# ESP32-3DE.net
KiCad netlist of a schematic drawn in Altium Designer
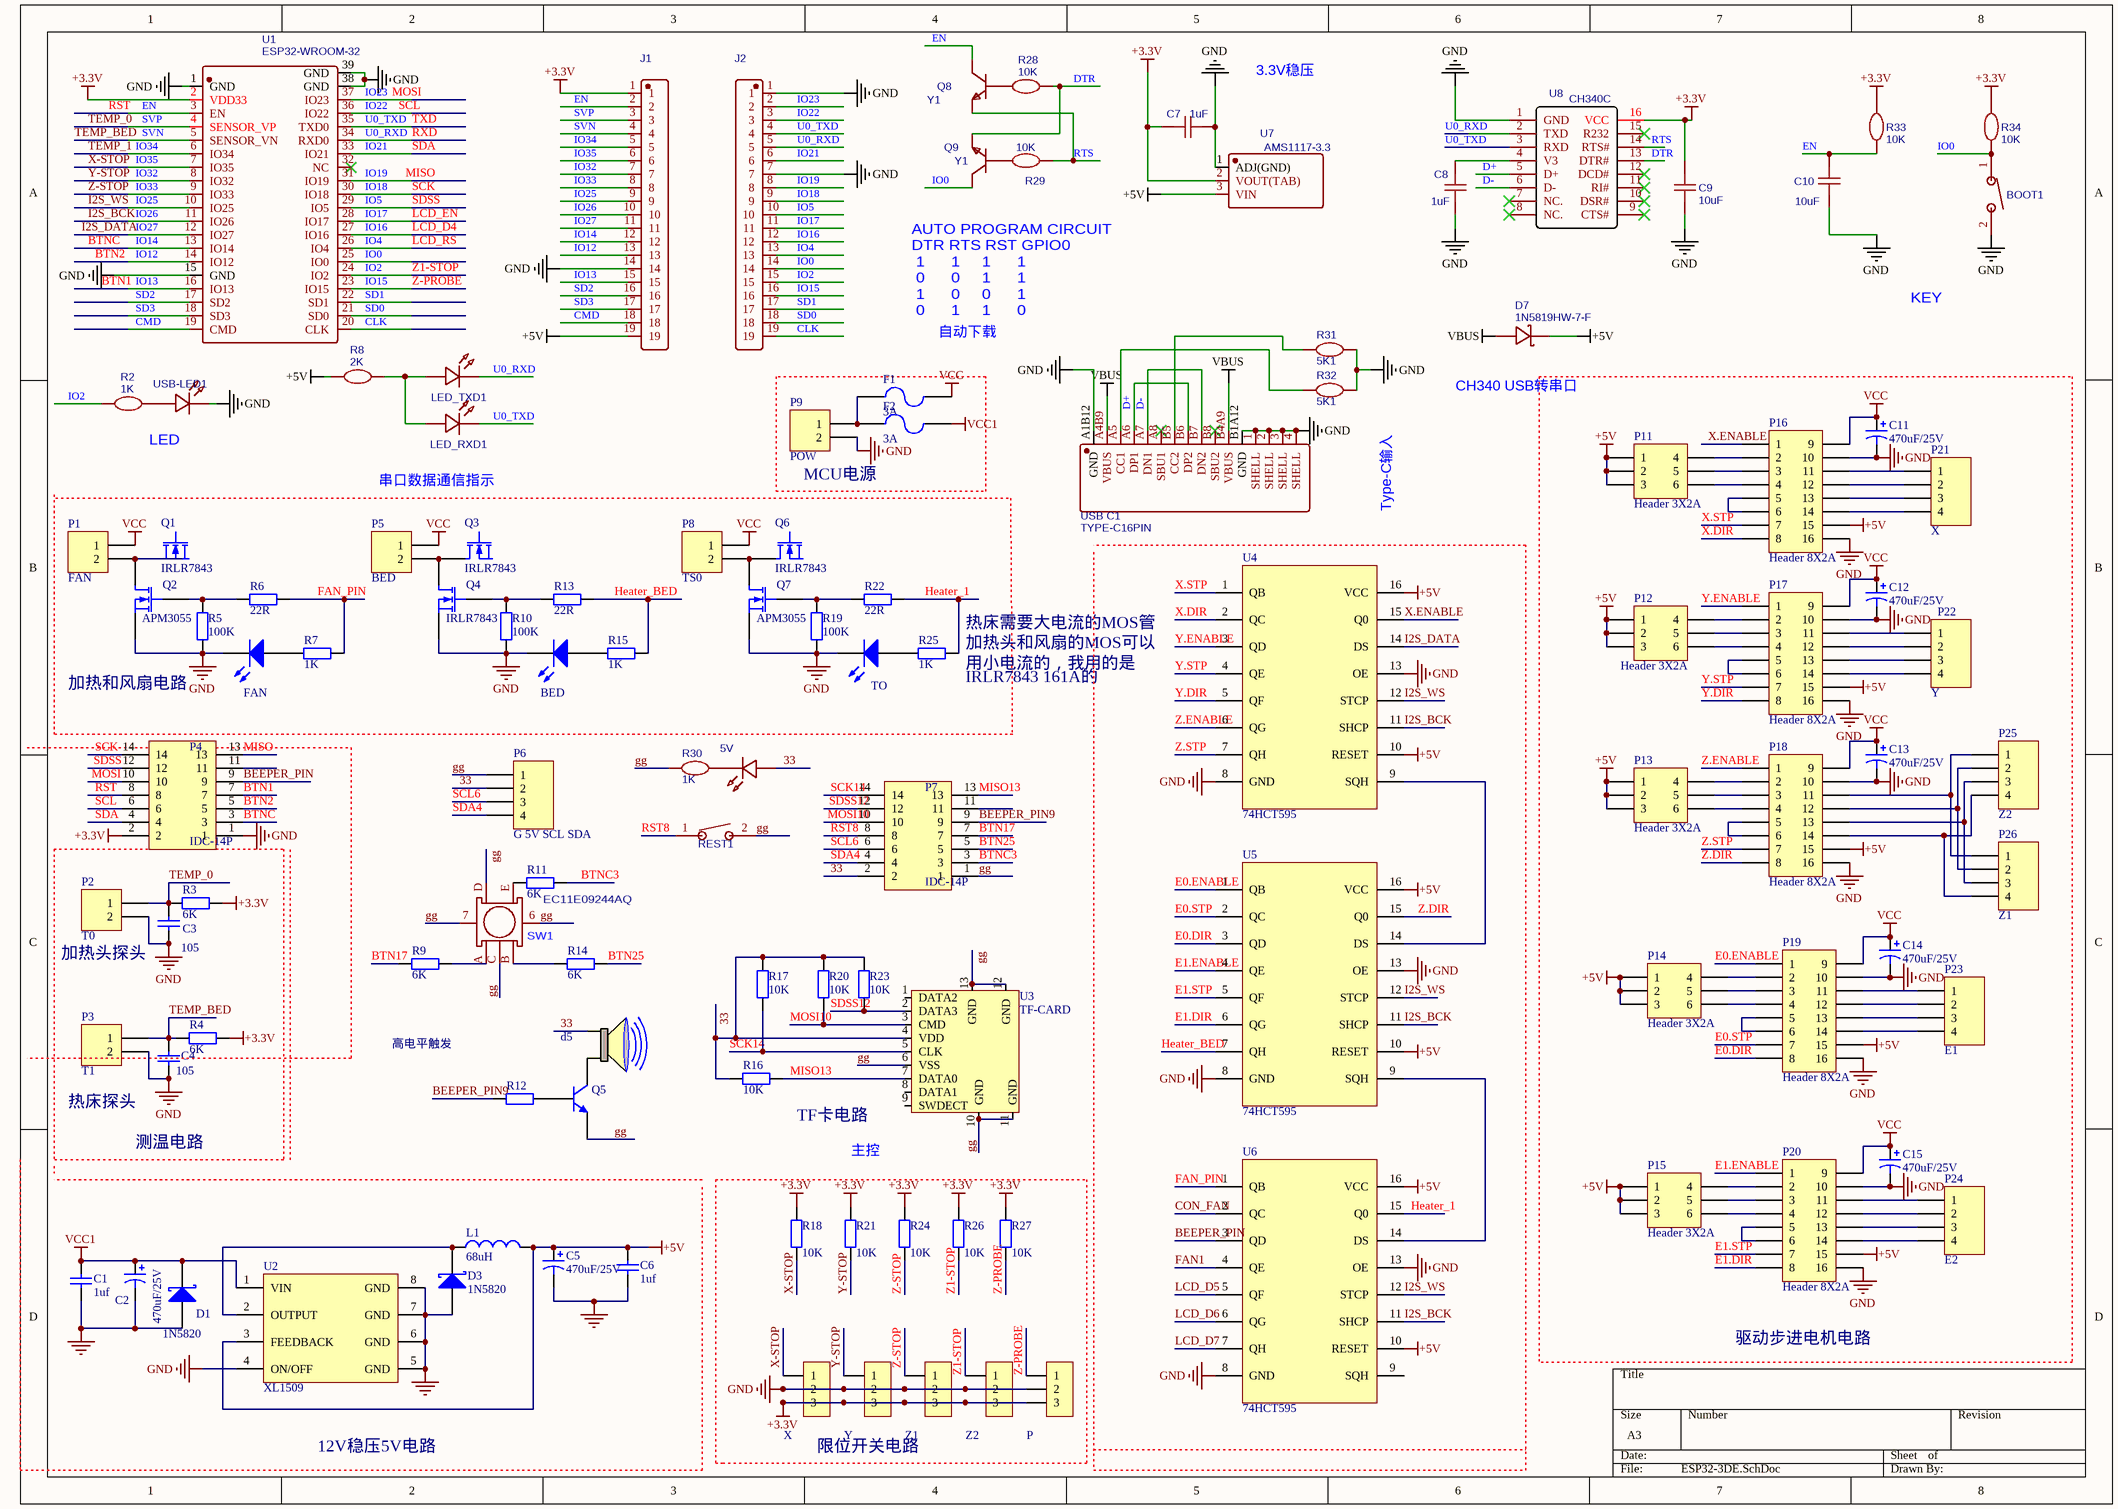
[diagram p0: ESP32-3DE.SchDoc]

(export (version "E")
  (design (tool "Eeschema 10.0.6"))
  (components
    (comp (ref "BOOT1")
      (value "BOOT")
      (footprint "SW-SMD_L4.0-W2.9-P4.15-EH")
      (fields
        (field (name "BOM_SUPPLIER PART") "C354947")
        (field (name "BOM_MANUFACTURER PART") "TSA343G00D-250J2")
        (field (name "CONTRIBUTOR") "LCSC")
      )
      (libsource (lib "altium-import") (part "root_3_TSA343G00D-250J2_"))
    )
    (comp (ref "C1")
      (value "1uf")
      (footprint "C0603")
      (description "Capacitor")
      (fields (field (name "PUBLISHER") "Altium Limited"))
      (libsource (lib "*") (part "Cap"))
    )
    (comp (ref "C2")
      (value "470uF/25V")
      (footprint "SMD-EC10X10X10")
      (description "Polarized Capacitor (Surface Mount)")
      (fields (field (name "PUBLISHER") "Altium Limited"))
      (libsource (lib "*") (part "Cap Pol3"))
    )
    (comp (ref "C3")
      (value "105")
      (footprint "C0603")
      (description "Capacitor")
      (fields (field (name "Comment") "1uf") (field (name "PUBLISHER") "Altium Limited"))
      (libsource (lib "Miscellaneous Devices") (part "Cap"))
    )
    (comp (ref "C4")
      (value "105")
      (footprint "C0603")
      (description "Capacitor")
      (fields (field (name "Comment") "1uf") (field (name "PUBLISHER") "Altium Limited"))
      (libsource (lib "Miscellaneous Devices") (part "Cap"))
    )
    (comp (ref "C5")
      (value "470uF/25V")
      (footprint "SMD-EC6.3X6.3X10")
      (description "Polarized Capacitor (Surface Mount)")
      (fields (field (name "PUBLISHER") "Altium Limited"))
      (libsource (lib "*") (part "Cap Pol3"))
    )
    (comp (ref "C6")
      (value "1uf")
      (footprint "C0603")
      (description "Capacitor")
      (fields (field (name "PUBLISHER") "Altium Limited"))
      (libsource (lib "*") (part "Cap"))
    )
    (comp (ref "C7")
      (value "1uF")
      (footprint "C0603")
      (fields (field (name "CONTRIBUTOR") "LCEDA_Lib"))
      (libsource (lib "altium-import") (part "root_0_10uF_"))
    )
    (comp (ref "C8")
      (value "1uF")
      (footprint "C0603")
      (fields
        (field (name "BOM_SUPPLIER PART") "C36577")
        (field (name "BOM_MANUFACTURER PART") "0603F105M250NT")
        (field (name "CONTRIBUTOR") "LCEDA_Lib")
      )
      (libsource (lib "altium-import") (part "root_1_1uF_"))
    )
    (comp (ref "C9")
      (value "10uF")
      (footprint "C0603")
      (fields (field (name "CONTRIBUTOR") "LCEDA_Lib"))
      (libsource (lib "altium-import") (part "root_1_10uF_"))
    )
    (comp (ref "C10")
      (value "10uF")
      (footprint "C0603")
      (fields (field (name "CONTRIBUTOR") "LCEDA_Lib"))
      (libsource (lib "altium-import") (part "root_1_10uF_"))
    )
    (comp (ref "C11")
      (value "470uF/25V")
      (footprint "SMD-EC6.3X6.3X10")
      (description "Polarized Capacitor (Radial)")
      (fields (field (name "Comment") "470UF") (field (name "PUBLISHER") "Altium Limited"))
      (libsource (lib "Miscellaneous Devices") (part "Cap Pol1"))
    )
    (comp (ref "C12")
      (value "470uF/25V")
      (footprint "SMD-EC6.3X6.3X10")
      (description "Polarized Capacitor (Radial)")
      (fields (field (name "Comment") "470UF") (field (name "PUBLISHER") "Altium Limited"))
      (libsource (lib "Miscellaneous Devices") (part "Cap Pol1"))
    )
    (comp (ref "C13")
      (value "470uF/25V")
      (footprint "SMD-EC6.3X6.3X10")
      (description "Polarized Capacitor (Radial)")
      (fields (field (name "Comment") "470UF") (field (name "PUBLISHER") "Altium Limited"))
      (libsource (lib "Miscellaneous Devices") (part "Cap Pol1"))
    )
    (comp (ref "C14")
      (value "470uF/25V")
      (footprint "SMD-EC6.3X6.3X10")
      (description "Polarized Capacitor (Radial)")
      (fields (field (name "Comment") "470UF") (field (name "PUBLISHER") "Altium Limited"))
      (libsource (lib "Miscellaneous Devices") (part "Cap Pol1"))
    )
    (comp (ref "C15")
      (value "470uF/25V")
      (footprint "SMD-EC6.3X6.3X10")
      (description "Polarized Capacitor (Radial)")
      (fields (field (name "Comment") "470UF") (field (name "PUBLISHER") "Altium Limited"))
      (libsource (lib "Miscellaneous Devices") (part "Cap Pol1"))
    )
    (comp (ref "D1")
      (value "1N5820")
      (footprint "SMA")
      (description "Schottky Diode")
      (fields (field (name "PUBLISHER") "Altium Limited"))
      (libsource (lib "Miscellaneous Devices") (part "D Schottky"))
    )
    (comp (ref "D2")
      (value "FAN")
      (footprint "LED 0603B")
      (description "Typical RED, GREEN, YELLOW, AMBER GaAs LED")
      (fields (field (name "PUBLISHER") "Altium Limited"))
      (libsource (lib "Miscellaneous Devices") (part "LED2"))
    )
    (comp (ref "D3")
      (value "1N5820")
      (footprint "SMA")
      (description "Schottky Diode")
      (fields (field (name "PUBLISHER") "Altium Limited"))
      (libsource (lib "Miscellaneous Devices") (part "D Schottky"))
    )
    (comp (ref "D4")
      (value "BED")
      (footprint "LED 0603B")
      (description "Typical RED, GREEN, YELLOW, AMBER GaAs LED")
      (fields (field (name "PUBLISHER") "Altium Limited"))
      (libsource (lib "Miscellaneous Devices") (part "LED2"))
    )
    (comp (ref "d5")
      (value "buzzer")
      (footprint "BEEP 5x9x5.5")
      (description "bu")
      (libsource (lib "YKY-arduinoRFID") (part "buzzer"))
    )
    (comp (ref "D6")
      (value "TO")
      (footprint "LED 0603B")
      (description "Typical RED, GREEN, YELLOW, AMBER GaAs LED")
      (fields (field (name "PUBLISHER") "Altium Limited"))
      (libsource (lib "Miscellaneous Devices") (part "LED2"))
    )
    (comp (ref "D7")
      (value "1N5819HW-7-F")
      (footprint "SOD-123_L2.8-W1.8-LS3.7-FD")
      (fields (field (name "BOM_SUPPLIER PART") "C82544"))
      (libsource (lib "altium-import") (part "root_0_1N5819HW-7-F_"))
    )
    (comp (ref "F1")
      (value "3A")
      (footprint "MCCQ-122")
      (description "Fuse")
      (fields (field (name "PUBLISHER") "Altium Limited"))
      (libsource (lib "Schlib1") (part "Fuse 2"))
    )
    (comp (ref "F2")
      (value "3A")
      (footprint "MCCQ-122")
      (description "Fuse")
      (fields (field (name "PUBLISHER") "Altium Limited"))
      (libsource (lib "Schlib1") (part "Fuse 2"))
    )
    (comp (ref "J1")
      (value "Header-Male-2.54_1x19")
      (footprint "HDR-TH_19P-P2.54-V-M-NOP")
      (fields
        (field (name "BOM_MANUFACTURER PART") "2.54mm 1*20PHeader")
        (field (name "BOM_SUPPLIER PART") "C50981")
        (field (name "CONTRIBUTOR") "shiyindebcd")
      )
      (libsource (lib "") (part "root_0_Header-Male-2.54_1x19__1"))
    )
    (comp (ref "J2")
      (value "Header-Male-2.54_1x19")
      (footprint "HDR-TH_19P-P2.54-V-M-NOP")
      (fields
        (field (name "BOM_MANUFACTURER PART") "2.54mm 1*20PHeader")
        (field (name "BOM_SUPPLIER PART") "C50981")
        (field (name "CONTRIBUTOR") "shiyindebcd")
      )
      (libsource (lib "altium-import") (part "root_0_Header-Male-2.54_1x19_"))
    )
    (comp (ref "JP1")
      (value "X")
      (footprint "XH2.54-LI-3P")
      (description "3P接插件")
      (fields (field (name "版权归属") "源创客"))
      (libsource (lib "Schlib1") (part "Header 3"))
    )
    (comp (ref "JP2")
      (value "Y")
      (footprint "XH2.54-LI-3P")
      (description "3P接插件")
      (fields (field (name "版权归属") "源创客"))
      (libsource (lib "Schlib1") (part "Header 3"))
    )
    (comp (ref "JP4")
      (value "Z1")
      (footprint "XH2.54-LI-3P")
      (description "3P接插件")
      (fields (field (name "版权归属") "源创客"))
      (libsource (lib "Schlib1") (part "Header 3"))
    )
    (comp (ref "JP5")
      (value "Z2")
      (footprint "XH2.54-LI-3P")
      (description "3P接插件")
      (fields (field (name "版权归属") "源创客"))
      (libsource (lib "Schlib1") (part "Header 3"))
    )
    (comp (ref "JP6")
      (value "P")
      (footprint "XH2.54-LI-3P")
      (description "3P接插件")
      (fields (field (name "版权归属") "源创客"))
      (libsource (lib "Schlib1") (part "Header 3"))
    )
    (comp (ref "L1")
      (value "68uH")
      (footprint "CDRH74")
      (description "Inductor")
      (fields (field (name "PUBLISHER") "Altium Limited"))
      (libsource (lib "*") (part "Inductor"))
    )
    (comp (ref "LED1")
      (value "5V")
      (footprint "LED 0603R")
      (fields
        (field (name "BOM_MANUFACTURER PART") "19-217/R6C-AL1M2VY/3T")
        (field (name "BOM_SUPPLIER PART") "C72044")
        (field (name "CONTRIBUTOR") "LCEDA_01")
      )
      (libsource (lib "altium-import") (part "root_2_IO2_"))
    )
    (comp (ref "LED_RXD1")
      (value "RXD")
      (footprint "LED 0603G")
      (fields
        (field (name "BOM_MANUFACTURER PART") "19-217/R6C-AL1M2VY/3T")
        (field (name "BOM_SUPPLIER PART") "C72044")
        (field (name "CONTRIBUTOR") "LCEDA_01")
      )
      (libsource (lib "altium-import") (part "root_0_RXD_"))
    )
    (comp (ref "LED_TXD1")
      (value "TXD")
      (footprint "LED 0603B")
      (fields
        (field (name "BOM_MANUFACTURER PART") "19-217/R6C-AL1M2VY/3T")
        (field (name "BOM_SUPPLIER PART") "C72044")
        (field (name "CONTRIBUTOR") "LCEDA_01")
      )
      (libsource (lib "altium-import") (part "root_0_TXD_"))
    )
    (comp (ref "P1")
      (value "FAN")
      (footprint "KF128-5.08-2P")
      (description "Header, 2-Pin")
      (fields (field (name "PUBLISHER") "Altium Limited"))
      (libsource (lib "Miscellaneous Connectors") (part "Header 2"))
    )
    (comp (ref "P2")
      (value "T0")
      (footprint "XH2.54-LI-2P")
      (description "Header, 2-Pin")
      (fields (field (name "PUBLISHER") "Altium Limited"))
      (libsource (lib "Miscellaneous Connectors") (part "Header 2"))
    )
    (comp (ref "P3")
      (value "T1")
      (footprint "XH2.54-LI-2P")
      (description "Header, 2-Pin")
      (fields (field (name "PUBLISHER") "Altium Limited"))
      (libsource (lib "Miscellaneous Connectors") (part "Header 2"))
    )
    (comp (ref "P4") (value "IDC-14P") (footprint "IDC2.54-14P") (libsource (lib "Schlib1") (part "IDC-14P")))
    (comp (ref "P5")
      (value "BED")
      (footprint "KF128-5.08-2P")
      (description "Header, 2-Pin")
      (fields (field (name "PUBLISHER") "Altium Limited"))
      (libsource (lib "Miscellaneous Connectors") (part "Header 2"))
    )
    (comp (ref "P6")
      (value "G 5V SCL SDA")
      (footprint "OLED-0.96-PIN4")
      (description "Header, 4-Pin")
      (fields (field (name "PUBLISHER") "Altium Limited"))
      (libsource (lib "Miscellaneous Connectors") (part "Header 4"))
    )
    (comp (ref "P7") (value "IDC-14P") (footprint "IDC2.54-14P") (libsource (lib "Schlib1") (part "IDC-14P")))
    (comp (ref "P8")
      (value "TS0")
      (footprint "KF128-5.08-2P")
      (description "Header, 2-Pin")
      (fields (field (name "PUBLISHER") "Altium Limited"))
      (libsource (lib "Miscellaneous Connectors") (part "Header 2"))
    )
    (comp (ref "P9")
      (value "POW")
      (footprint "KF128-5.08-2P")
      (description "Header, 2-Pin")
      (fields (field (name "PUBLISHER") "Altium Limited"))
      (libsource (lib "Miscellaneous Connectors") (part "Header 2"))
    )
    (comp (ref "P11")
      (value "Header 3X2A")
      (footprint "HDR2X3_CEN")
      (description "Header, 3-Pin, Dual row")
      (fields (field (name "PUBLISHER") "Altium Limited"))
      (libsource (lib "Miscellaneous Connectors") (part "Header 3X2A"))
    )
    (comp (ref "P12")
      (value "Header 3X2A")
      (footprint "HDR2X3_CEN")
      (description "Header, 3-Pin, Dual row")
      (fields (field (name "PUBLISHER") "Altium Limited"))
      (libsource (lib "Miscellaneous Connectors") (part "Header 3X2A"))
    )
    (comp (ref "P13")
      (value "Header 3X2A")
      (footprint "HDR2X3_CEN")
      (description "Header, 3-Pin, Dual row")
      (fields (field (name "PUBLISHER") "Altium Limited"))
      (libsource (lib "Miscellaneous Connectors") (part "Header 3X2A"))
    )
    (comp (ref "P14")
      (value "Header 3X2A")
      (footprint "HDR2X3_CEN")
      (description "Header, 3-Pin, Dual row")
      (fields (field (name "PUBLISHER") "Altium Limited"))
      (libsource (lib "Miscellaneous Connectors") (part "Header 3X2A"))
    )
    (comp (ref "P15")
      (value "Header 3X2A")
      (footprint "HDR2X3_CEN")
      (description "Header, 3-Pin, Dual row")
      (fields (field (name "PUBLISHER") "Altium Limited"))
      (libsource (lib "Miscellaneous Connectors") (part "Header 3X2A"))
    )
    (comp (ref "P16")
      (value "Header 8X2A")
      (footprint "A4988")
      (description "Header, 8-Pin, Dual row")
      (fields (field (name "PUBLISHER") "Altium Limited"))
      (libsource (lib "Miscellaneous Connectors") (part "Header 8X2A"))
    )
    (comp (ref "P17")
      (value "Header 8X2A")
      (footprint "A4988")
      (description "Header, 8-Pin, Dual row")
      (fields (field (name "PUBLISHER") "Altium Limited"))
      (libsource (lib "Miscellaneous Connectors") (part "Header 8X2A"))
    )
    (comp (ref "P18")
      (value "Header 8X2A")
      (footprint "A4988")
      (description "Header, 8-Pin, Dual row")
      (fields (field (name "PUBLISHER") "Altium Limited"))
      (libsource (lib "Miscellaneous Connectors") (part "Header 8X2A"))
    )
    (comp (ref "P19")
      (value "Header 8X2A")
      (footprint "A4988")
      (description "Header, 8-Pin, Dual row")
      (fields (field (name "PUBLISHER") "Altium Limited"))
      (libsource (lib "Miscellaneous Connectors") (part "Header 8X2A"))
    )
    (comp (ref "P20")
      (value "Header 8X2A")
      (footprint "A4988")
      (description "Header, 8-Pin, Dual row")
      (fields (field (name "PUBLISHER") "Altium Limited"))
      (libsource (lib "Miscellaneous Connectors") (part "Header 8X2A"))
    )
    (comp (ref "P21")
      (value "X")
      (footprint "XH2.54-LI-4P")
      (description "Header, 4-Pin")
      (fields (field (name "PUBLISHER") "Altium Limited"))
      (libsource (lib "Miscellaneous Connectors") (part "Header 4"))
    )
    (comp (ref "P22")
      (value "Y")
      (footprint "XH2.54-LI-4P")
      (description "Header, 4-Pin")
      (fields (field (name "PUBLISHER") "Altium Limited"))
      (libsource (lib "Miscellaneous Connectors") (part "Header 4"))
    )
    (comp (ref "P23")
      (value "E1")
      (footprint "XH2.54-LI-4P")
      (description "Header, 4-Pin")
      (fields (field (name "PUBLISHER") "Altium Limited"))
      (libsource (lib "Miscellaneous Connectors") (part "Header 4"))
    )
    (comp (ref "P24")
      (value "E2")
      (footprint "XH2.54-LI-4P")
      (description "Header, 4-Pin")
      (fields (field (name "PUBLISHER") "Altium Limited"))
      (libsource (lib "Miscellaneous Connectors") (part "Header 4"))
    )
    (comp (ref "P25")
      (value "Z2")
      (footprint "XH2.54-LI-4P")
      (description "Header, 4-Pin")
      (fields (field (name "PUBLISHER") "Altium Limited"))
      (libsource (lib "Miscellaneous Connectors") (part "Header 4"))
    )
    (comp (ref "P26")
      (value "Z1")
      (footprint "XH2.54-LI-4P")
      (description "Header, 4-Pin")
      (fields (field (name "PUBLISHER") "Altium Limited"))
      (libsource (lib "Miscellaneous Connectors") (part "Header 4"))
    )
    (comp (ref "Q1")
      (value "IRLR7843")
      (footprint "TO-252gk")
      (description "N-Channel MOSFET")
      (fields (field (name "PUBLISHER") "Altium Limited"))
      (libsource (lib "Schlib1") (part "MOSFET-Ngk"))
    )
    (comp (ref "Q2")
      (value "APM3055")
      (footprint "TO-252")
      (description "N-Channel MOSFET")
      (fields (field (name "PUBLISHER") "Altium Limited"))
      (libsource (lib "Miscellaneous Devices") (part "MOSFET-N"))
    )
    (comp (ref "Q3")
      (value "IRLR7843")
      (footprint "TO-252gk")
      (description "N-Channel MOSFET")
      (fields (field (name "PUBLISHER") "Altium Limited"))
      (libsource (lib "Schlib1") (part "MOSFET-Ngk"))
    )
    (comp (ref "Q4")
      (value "IRLR7843")
      (footprint "TO-252")
      (description "N-Channel MOSFET")
      (fields (field (name "PUBLISHER") "Altium Limited"))
      (libsource (lib "Miscellaneous Devices") (part "MOSFET-N"))
    )
    (comp (ref "Q5")
      (value "Y1")
      (footprint "SOT-23-3")
      (description "SS8050 Y1三极管")
      (libsource (lib "YKY-arduinoRFID") (part "SOT-23 SS8050 Y1"))
    )
    (comp (ref "Q6")
      (value "IRLR7843")
      (footprint "TO-252gk")
      (description "N-Channel MOSFET")
      (fields (field (name "PUBLISHER") "Altium Limited"))
      (libsource (lib "Schlib1") (part "MOSFET-Ngk"))
    )
    (comp (ref "Q7")
      (value "APM3055")
      (footprint "TO-252")
      (description "N-Channel MOSFET")
      (fields (field (name "PUBLISHER") "Altium Limited"))
      (libsource (lib "Miscellaneous Devices") (part "MOSFET-N"))
    )
    (comp (ref "Q8")
      (value "Y1")
      (footprint "SOT-23-3")
      (fields
        (field (name "BOM_SUPPLIER PART") "C2688231")
        (field (name "BOM_MANUFACTURER PART") "S8050")
        (field (name "CONTRIBUTOR") "LCSC")
      )
      (libsource (lib "altium-import") (part "root_0_S8050_"))
    )
    (comp (ref "Q9")
      (value "Y1")
      (footprint "SOT-23-3")
      (fields
        (field (name "BOM_SUPPLIER PART") "C2688231")
        (field (name "BOM_MANUFACTURER PART") "S8050")
        (field (name "CONTRIBUTOR") "LCSC")
      )
      (libsource (lib "altium-import") (part "root_2_S8050_"))
    )
    (comp (ref "R2")
      (value "1K")
      (footprint "R0603")
      (fields (field (name "CONTRIBUTOR") "LCEDA_Lib"))
      (libsource (lib "altium-import") (part "root_0_1K_"))
    )
    (comp (ref "R3")
      (value "6K")
      (footprint "R0603")
      (description "Resistor")
      (fields (field (name "PUBLISHER") "Altium Limited"))
      (libsource (lib "") (part "Res2_1"))
    )
    (comp (ref "R4")
      (value "6K")
      (footprint "R0603")
      (description "Resistor")
      (fields (field (name "PUBLISHER") "Altium Limited"))
      (libsource (lib "") (part "Res2_3"))
    )
    (comp (ref "R5")
      (value "100K")
      (footprint "R0603")
      (description "Resistor")
      (fields (field (name "PUBLISHER") "Altium Limited"))
      (libsource (lib "") (part "Res2_2"))
    )
    (comp (ref "R6")
      (value "22R")
      (footprint "R0603")
      (description "Resistor")
      (fields (field (name "PUBLISHER") "Altium Limited"))
      (libsource (lib "") (part "Res2_1"))
    )
    (comp (ref "R7")
      (value "1K")
      (footprint "R0603")
      (description "Resistor")
      (fields (field (name "PUBLISHER") "Altium Limited"))
      (libsource (lib "") (part "Res2_1"))
    )
    (comp (ref "R8")
      (value "2K")
      (footprint "R0603")
      (fields (field (name "CONTRIBUTOR") "LCEDA_Lib"))
      (libsource (lib "altium-import") (part "root_0_2K_"))
    )
    (comp (ref "R9")
      (value "6K")
      (footprint "R0603")
      (description "Resistor")
      (fields (field (name "PUBLISHER") "Altium Limited"))
      (libsource (lib "") (part "Res2_3"))
    )
    (comp (ref "R10")
      (value "100K")
      (footprint "R0603")
      (description "Resistor")
      (fields (field (name "PUBLISHER") "Altium Limited"))
      (libsource (lib "") (part "Res2_2"))
    )
    (comp (ref "R11")
      (value "6K")
      (footprint "R0603")
      (description "Resistor")
      (fields (field (name "PUBLISHER") "Altium Limited"))
      (libsource (lib "") (part "Res2_1"))
    )
    (comp (ref "R12")
      (value "4.7K")
      (footprint "R0603")
      (description "4.7KΩ (4701) ±1%贴片电阻")
      (libsource (lib "YKY-arduinoRFID") (part "0805 4.7KΩ (4701) 1%"))
    )
    (comp (ref "R13")
      (value "22R")
      (footprint "R0603")
      (description "Resistor")
      (fields (field (name "PUBLISHER") "Altium Limited"))
      (libsource (lib "") (part "Res2_1"))
    )
    (comp (ref "R14")
      (value "6K")
      (footprint "R0603")
      (description "Resistor")
      (fields (field (name "PUBLISHER") "Altium Limited"))
      (libsource (lib "") (part "Res2_3"))
    )
    (comp (ref "R15")
      (value "1K")
      (footprint "R0603")
      (description "Resistor")
      (fields (field (name "PUBLISHER") "Altium Limited"))
      (libsource (lib "") (part "Res2_1"))
    )
    (comp (ref "R16")
      (value "10K")
      (footprint "R0603")
      (description "Resistor")
      (fields (field (name "PUBLISHER") "Altium Limited"))
      (libsource (lib "") (part "Res2_3"))
    )
    (comp (ref "R17")
      (value "10K")
      (footprint "R0603")
      (description "Resistor")
      (fields (field (name "PUBLISHER") "Altium Limited"))
      (libsource (lib "Miscellaneous Devices") (part "Res2"))
    )
    (comp (ref "R18")
      (value "10K")
      (footprint "R0603")
      (description "Resistor")
      (fields (field (name "PUBLISHER") "Altium Limited"))
      (libsource (lib "") (part "Res2_2"))
    )
    (comp (ref "R19")
      (value "100K")
      (footprint "R0603")
      (description "Resistor")
      (fields (field (name "PUBLISHER") "Altium Limited"))
      (libsource (lib "") (part "Res2_2"))
    )
    (comp (ref "R20")
      (value "10K")
      (footprint "R0603")
      (description "Resistor")
      (fields (field (name "PUBLISHER") "Altium Limited"))
      (libsource (lib "Miscellaneous Devices") (part "Res2"))
    )
    (comp (ref "R21")
      (value "10K")
      (footprint "R0603")
      (description "Resistor")
      (fields (field (name "PUBLISHER") "Altium Limited"))
      (libsource (lib "") (part "Res2_2"))
    )
    (comp (ref "R22")
      (value "22R")
      (footprint "R0603")
      (description "Resistor")
      (fields (field (name "PUBLISHER") "Altium Limited"))
      (libsource (lib "") (part "Res2_1"))
    )
    (comp (ref "R23")
      (value "10K")
      (footprint "R0603")
      (description "Resistor")
      (fields (field (name "PUBLISHER") "Altium Limited"))
      (libsource (lib "Miscellaneous Devices") (part "Res2"))
    )
    (comp (ref "R24")
      (value "10K")
      (footprint "R0603")
      (description "Resistor")
      (fields (field (name "PUBLISHER") "Altium Limited"))
      (libsource (lib "") (part "Res2_2"))
    )
    (comp (ref "R25")
      (value "1K")
      (footprint "R0603")
      (description "Resistor")
      (fields (field (name "PUBLISHER") "Altium Limited"))
      (libsource (lib "") (part "Res2_1"))
    )
    (comp (ref "R26")
      (value "10K")
      (footprint "R0603")
      (description "Resistor")
      (fields (field (name "PUBLISHER") "Altium Limited"))
      (libsource (lib "") (part "Res2_2"))
    )
    (comp (ref "R27")
      (value "10K")
      (footprint "R0603")
      (description "Resistor")
      (fields (field (name "PUBLISHER") "Altium Limited"))
      (libsource (lib "") (part "Res2_2"))
    )
    (comp (ref "R28")
      (value "10K")
      (footprint "R0603")
      (fields (field (name "CONTRIBUTOR") "LCEDA_Lib"))
      (libsource (lib "altium-import") (part "root_0_10K_"))
    )
    (comp (ref "R29")
      (value "10K")
      (footprint "R0603")
      (fields (field (name "CONTRIBUTOR") "LCEDA_Lib"))
      (libsource (lib "altium-import") (part "root_0_10K_"))
    )
    (comp (ref "R30")
      (value "1K")
      (footprint "R0603")
      (fields (field (name "CONTRIBUTOR") "LCEDA_Lib"))
      (libsource (lib "Schlib1") (part "1K"))
    )
    (comp (ref "R31")
      (value "5K1")
      (footprint "R0603")
      (fields (field (name "CONTRIBUTOR") "LCEDA_Lib"))
      (libsource (lib "Miscellaneous Devices") (part "5K1"))
    )
    (comp (ref "R32")
      (value "5K1")
      (footprint "R0603")
      (fields (field (name "CONTRIBUTOR") "LCEDA_Lib"))
      (libsource (lib "Schlib1") (part "5K1"))
    )
    (comp (ref "R33")
      (value "10K")
      (footprint "R0603")
      (fields (field (name "CONTRIBUTOR") "LCEDA_Lib"))
      (libsource (lib "altium-import") (part "root_1_10K_"))
    )
    (comp (ref "R34")
      (value "10K")
      (footprint "R0603")
      (fields (field (name "CONTRIBUTOR") "LCEDA_Lib"))
      (libsource (lib "altium-import") (part "root_1_10K_"))
    )
    (comp (ref "REST1")
      (value "REST")
      (footprint "SMD-6X6X6")
      (fields
        (field (name "BOM_SUPPLIER PART") "C354947")
        (field (name "BOM_MANUFACTURER PART") "TSA343G00D-250J2")
        (field (name "CONTRIBUTOR") "LCSC")
      )
      (libsource (lib "altium-import") (part "root_0_TSA343G00D-250J2_"))
    )
    (comp (ref "SW1")
      (value "EC11E09244AQ")
      (footprint "SW-TH_EC11E15244G1")
      (libsource (lib "Schlib1") (part "EC11E09244AQ"))
    )
    (comp (ref "U1")
      (value "ESP32-WROOM-32")
      (footprint "WIFIM-SMD_39P-L25.5-W18.0-P1.27")
      (fields (field (name "BOM_SUPPLIER PART") "C503587") (field (name "CONTRIBUTOR") "LCSC"))
      (libsource (lib "altium-import") (part "root_0_ESP32-WROOM-32_"))
    )
    (comp (ref "U2")
      (value "XL1509")
      (footprint "SOP8 - duplicate")
      (libsource (lib "Schlib1") (part "Component_1"))
    )
    (comp (ref "U3") (value "TF-CARD") (footprint "MicroSD") (libsource (lib "Schlib1") (part "TF2")))
    (comp (ref "U4")
      (value "74HCT595")
      (footprint "SOP16_1.27mm")
      (libsource (lib "Schlib1") (part "74HCT595"))
    )
    (comp (ref "U5")
      (value "74HCT595")
      (footprint "SOP16_1.27mm")
      (libsource (lib "Schlib1") (part "74HCT595"))
    )
    (comp (ref "U6")
      (value "74HCT595")
      (footprint "SOP16_1.27mm")
      (libsource (lib "Schlib1") (part "74HCT595"))
    )
    (comp (ref "U7")
      (value "AMS1117-3.3")
      (footprint "SOT-223-4_L6.5-W3.5-P2.30-LS7.0-BR")
      (fields (field (name "BOM_SUPPLIER PART") "C347256") (field (name "CONTRIBUTOR") "LCSC"))
      (libsource (lib "altium-import") (part "root_0_AMS1117-3.3_C347256_"))
    )
    (comp (ref "U8")
      (value "CH340C")
      (footprint "SOP-16_L10.0-W3.9-P1.27-LS6.0-BL")
      (fields (field (name "BOM_SUPPLIER PART") "C84681"))
      (libsource (lib "altium-import") (part "root_0_CH340C_"))
    )
    (comp (ref "USB C1")
      (value "TYPE-C16PIN")
      (footprint "USB-C-SMD_TYPE-C16PIN")
      (fields (field (name "BOM_SUPPLIER PART") "C393939") (field (name "CONTRIBUTOR") "LCSC"))
      (libsource (lib "altium-import") (part "root_1_TYPE-C16PIN_"))
    )
    (comp (ref "USB-LED1")
      (value "LED-0603_R")
      (footprint "LED 0603R")
      (fields
        (field (name "BOM_MANUFACTURER PART") "19-217/R6C-AL1M2VY/3T")
        (field (name "BOM_SUPPLIER PART") "C72044")
        (field (name "CONTRIBUTOR") "LCEDA_01")
      )
      (libsource (lib "altium-import") (part "root_0_LED-0603_R_"))
    )
  )
  (nets
    (net (code "1") (name "+3.3V") (class "Default")
      (node (ref "C7") (pin "1") (pinfunction "1_1") (pintype "passive"))
      (node (ref "C9") (pin "2") (pinfunction "2_2") (pintype "passive"))
      (node (ref "J1") (pin "1") (pinfunction "1_1") (pintype "passive"))
      (node (ref "JP1") (pin "3") (pinfunction "3_3") (pintype "passive"))
      (node (ref "JP2") (pin "3") (pinfunction "3_3") (pintype "passive"))
      (node (ref "JP4") (pin "3") (pinfunction "3_3") (pintype "passive"))
      (node (ref "JP5") (pin "3") (pinfunction "3_3") (pintype "passive"))
      (node (ref "JP6") (pin "3") (pinfunction "3_3") (pintype "passive"))
      (node (ref "P4") (pin "2") (pinfunction "2_2") (pintype "passive"))
      (node (ref "R18") (pin "2") (pinfunction "2_2") (pintype "passive"))
      (node (ref "R21") (pin "2") (pinfunction "2_2") (pintype "passive"))
      (node (ref "R24") (pin "2") (pinfunction "2_2") (pintype "passive"))
      (node (ref "R26") (pin "2") (pinfunction "2_2") (pintype "passive"))
      (node (ref "R27") (pin "2") (pinfunction "2_2") (pintype "passive"))
      (node (ref "R3") (pin "1") (pinfunction "1_1") (pintype "passive"))
      (node (ref "R33") (pin "2") (pinfunction "2_2") (pintype "passive"))
      (node (ref "R34") (pin "2") (pinfunction "2_2") (pintype "passive"))
      (node (ref "R4") (pin "2") (pinfunction "2_2") (pintype "passive"))
      (node (ref "U1") (pin "2") (pinfunction "VDD33_2") (pintype "passive"))
      (node (ref "U7") (pin "2") (pinfunction "VOUT(TAB)_2") (pintype "passive"))
      (node (ref "U8") (pin "16") (pinfunction "VCC_16") (pintype "passive"))
    )
    (net (code "2") (name "+5V") (class "Default")
      (node (ref "C5") (pin "1") (pinfunction "1_1") (pintype "passive"))
      (node (ref "C6") (pin "2") (pinfunction "2_2") (pintype "passive"))
      (node (ref "D7") (pin "2") (pinfunction "K_2") (pintype "passive"))
      (node (ref "J1") (pin "19") (pinfunction "19_19") (pintype "passive"))
      (node (ref "L1") (pin "2") (pinfunction "2_2") (pintype "passive"))
      (node (ref "P11") (pin "1") (pinfunction "1_1") (pintype "passive"))
      (node (ref "P11") (pin "2") (pinfunction "2_2") (pintype "passive"))
      (node (ref "P11") (pin "3") (pinfunction "3_3") (pintype "passive"))
      (node (ref "P12") (pin "1") (pinfunction "1_1") (pintype "passive"))
      (node (ref "P12") (pin "2") (pinfunction "2_2") (pintype "passive"))
      (node (ref "P12") (pin "3") (pinfunction "3_3") (pintype "passive"))
      (node (ref "P13") (pin "1") (pinfunction "1_1") (pintype "passive"))
      (node (ref "P13") (pin "2") (pinfunction "2_2") (pintype "passive"))
      (node (ref "P13") (pin "3") (pinfunction "3_3") (pintype "passive"))
      (node (ref "P14") (pin "1") (pinfunction "1_1") (pintype "passive"))
      (node (ref "P14") (pin "2") (pinfunction "2_2") (pintype "passive"))
      (node (ref "P14") (pin "3") (pinfunction "3_3") (pintype "passive"))
      (node (ref "P15") (pin "1") (pinfunction "1_1") (pintype "passive"))
      (node (ref "P15") (pin "2") (pinfunction "2_2") (pintype "passive"))
      (node (ref "P15") (pin "3") (pinfunction "3_3") (pintype "passive"))
      (node (ref "P16") (pin "15") (pinfunction "15_15") (pintype "passive"))
      (node (ref "P17") (pin "15") (pinfunction "15_15") (pintype "passive"))
      (node (ref "P18") (pin "15") (pinfunction "15_15") (pintype "passive"))
      (node (ref "P19") (pin "15") (pinfunction "15_15") (pintype "passive"))
      (node (ref "P20") (pin "15") (pinfunction "15_15") (pintype "passive"))
      (node (ref "R8") (pin "1") (pinfunction "1_1") (pintype "passive"))
      (node (ref "U2") (pin "3") (pinfunction "FEEDBACK_3") (pintype "passive"))
      (node (ref "U4") (pin "10") (pinfunction "RESET_10") (pintype "passive"))
      (node (ref "U4") (pin "16") (pinfunction "VCC_16") (pintype "passive"))
      (node (ref "U5") (pin "10") (pinfunction "RESET_10") (pintype "passive"))
      (node (ref "U5") (pin "16") (pinfunction "VCC_16") (pintype "passive"))
      (node (ref "U6") (pin "10") (pinfunction "RESET_10") (pintype "passive"))
      (node (ref "U6") (pin "16") (pinfunction "VCC_16") (pintype "passive"))
      (node (ref "U7") (pin "3") (pinfunction "VIN_3") (pintype "passive"))
    )
    (net (code "3") (name "/33") (class "Default")
      (node (ref "LED1") (pin "1") (pinfunction "1_1") (pintype "passive"))
      (node (ref "P6") (pin "2") (pinfunction "2_2") (pintype "passive"))
      (node (ref "P7") (pin "2") (pinfunction "2_2") (pintype "passive"))
      (node (ref "R16") (pin "1") (pinfunction "1_1") (pintype "passive"))
      (node (ref "R17") (pin "1") (pinfunction "1_1") (pintype "passive"))
      (node (ref "R20") (pin "1") (pinfunction "1_1") (pintype "passive"))
      (node (ref "R23") (pin "1") (pinfunction "1_1") (pintype "passive"))
      (node (ref "U3") (pin "4") (pinfunction "VDD_4") (pintype "passive"))
      (node (ref "d5") (pin "1") (pinfunction "1_1") (pintype "passive"))
    )
    (net (code "4") (name "/BEEPER_PIN") (class "Default")
      (node (ref "P4") (pin "9") (pinfunction "9_9") (pintype "passive"))
      (node (ref "U6") (pin "3") (pinfunction "QD_3") (pintype "passive"))
    )
    (net (code "5") (name "/BEEPER_PIN9") (class "Default")
      (node (ref "P7") (pin "9") (pinfunction "9_9") (pintype "passive"))
      (node (ref "R12") (pin "1") (pinfunction "1_1") (pintype "passive"))
    )
    (net (code "6") (name "/BTN1") (class "Default")
      (node (ref "J1") (pin "15") (pinfunction "15_15") (pintype "passive"))
      (node (ref "P4") (pin "7") (pinfunction "7_7") (pintype "passive"))
      (node (ref "U1") (pin "16") (pinfunction "IO13_16") (pintype "passive"))
    )
    (net (code "7") (name "/BTN2") (class "Default")
      (node (ref "J1") (pin "13") (pinfunction "13_13") (pintype "passive"))
      (node (ref "P4") (pin "5") (pinfunction "5_5") (pintype "passive"))
      (node (ref "U1") (pin "14") (pinfunction "IO12_14") (pintype "passive"))
    )
    (net (code "8") (name "/BTN17") (class "Default")
      (node (ref "P7") (pin "7") (pinfunction "7_7") (pintype "passive"))
      (node (ref "R9") (pin "1") (pinfunction "1_1") (pintype "passive"))
    )
    (net (code "9") (name "/BTN25") (class "Default")
      (node (ref "P7") (pin "5") (pinfunction "5_5") (pintype "passive"))
      (node (ref "R14") (pin "2") (pinfunction "2_2") (pintype "passive"))
    )
    (net (code "10") (name "/BTNC") (class "Default")
      (node (ref "J1") (pin "12") (pinfunction "12_12") (pintype "passive"))
      (node (ref "P4") (pin "3") (pinfunction "3_3") (pintype "passive"))
      (node (ref "U1") (pin "13") (pinfunction "IO14_13") (pintype "passive"))
    )
    (net (code "11") (name "/BTNC3") (class "Default")
      (node (ref "P7") (pin "3") (pinfunction "3_3") (pintype "passive"))
      (node (ref "R11") (pin "1") (pinfunction "1_1") (pintype "passive"))
    )
    (net (code "12") (name "/CLK") (class "Default")
      (node (ref "J2") (pin "19") (pinfunction "19_19") (pintype "passive"))
      (node (ref "U1") (pin "20") (pinfunction "CLK_20") (pintype "passive"))
    )
    (net (code "13") (name "/CMD") (class "Default")
      (node (ref "J1") (pin "18") (pinfunction "18_18") (pintype "passive"))
      (node (ref "U1") (pin "19") (pinfunction "CMD_19") (pintype "passive"))
    )
    (net (code "14") (name "/CON_FAN") (class "Default")
      (node (ref "U6") (pin "2") (pinfunction "QC_2") (pintype "passive"))
    )
    (net (code "15") (name "/D+") (class "Default")
      (node (ref "U8") (pin "5") (pinfunction "D+_5") (pintype "passive"))
      (node (ref "USB C1") (pin "A6") (pinfunction "DP1_A6") (pintype "passive"))
      (node (ref "USB C1") (pin "B6") (pinfunction "DP2_B6") (pintype "passive"))
    )
    (net (code "16") (name "/D-") (class "Default")
      (node (ref "U8") (pin "6") (pinfunction "D-_6") (pintype "passive"))
      (node (ref "USB C1") (pin "A7") (pinfunction "DN1_A7") (pintype "passive"))
      (node (ref "USB C1") (pin "B7") (pinfunction "DN2_B7") (pintype "passive"))
    )
    (net (code "17") (name "/DTR") (class "Default")
      (node (ref "Q9") (pin "2") (pinfunction "E_2") (pintype "passive"))
      (node (ref "R28") (pin "2") (pinfunction "2_2") (pintype "passive"))
      (node (ref "U8") (pin "13") (pinfunction "DTR#_13") (pintype "passive"))
    )
    (net (code "18") (name "/E0.DIR") (class "Default")
      (node (ref "P19") (pin "8") (pinfunction "8_8") (pintype "passive"))
      (node (ref "U5") (pin "3") (pinfunction "QD_3") (pintype "passive"))
    )
    (net (code "19") (name "/E0.ENABLE") (class "Default")
      (node (ref "P19") (pin "1") (pinfunction "1_1") (pintype "passive"))
      (node (ref "U5") (pin "1") (pinfunction "QB_1") (pintype "passive"))
    )
    (net (code "20") (name "/E0.STP") (class "Default")
      (node (ref "P19") (pin "7") (pinfunction "7_7") (pintype "passive"))
      (node (ref "U5") (pin "2") (pinfunction "QC_2") (pintype "passive"))
    )
    (net (code "21") (name "/E1.DIR") (class "Default")
      (node (ref "P20") (pin "8") (pinfunction "8_8") (pintype "passive"))
      (node (ref "U5") (pin "6") (pinfunction "QG_6") (pintype "passive"))
    )
    (net (code "22") (name "/E1.ENABLE") (class "Default")
      (node (ref "P20") (pin "1") (pinfunction "1_1") (pintype "passive"))
      (node (ref "U5") (pin "4") (pinfunction "QE_4") (pintype "passive"))
    )
    (net (code "23") (name "/E1.STP") (class "Default")
      (node (ref "P20") (pin "7") (pinfunction "7_7") (pintype "passive"))
      (node (ref "U5") (pin "5") (pinfunction "QF_5") (pintype "passive"))
    )
    (net (code "24") (name "/EN") (class "Default")
      (node (ref "C10") (pin "2") (pinfunction "2_2") (pintype "passive"))
      (node (ref "J1") (pin "2") (pinfunction "2_2") (pintype "passive"))
      (node (ref "P4") (pin "8") (pinfunction "8_8") (pintype "passive"))
      (node (ref "Q8") (pin "3") (pinfunction "C_3") (pintype "passive"))
      (node (ref "R33") (pin "1") (pinfunction "1_1") (pintype "passive"))
      (node (ref "U1") (pin "3") (pinfunction "EN_3") (pintype "passive"))
    )
    (net (code "25") (name "/FAN1") (class "Default")
      (node (ref "U6") (pin "4") (pinfunction "QE_4") (pintype "passive"))
    )
    (net (code "26") (name "/FAN_PIN") (class "Default")
      (node (ref "R6") (pin "1") (pinfunction "1_1") (pintype "passive"))
      (node (ref "R7") (pin "1") (pinfunction "1_1") (pintype "passive"))
      (node (ref "U6") (pin "1") (pinfunction "QB_1") (pintype "passive"))
    )
    (net (code "27") (name "/Heater_1") (class "Default")
      (node (ref "R22") (pin "1") (pinfunction "1_1") (pintype "passive"))
      (node (ref "R25") (pin "1") (pinfunction "1_1") (pintype "passive"))
      (node (ref "U6") (pin "15") (pinfunction "Q0_15") (pintype "passive"))
    )
    (net (code "28") (name "/Heater_BED") (class "Default")
      (node (ref "R13") (pin "1") (pinfunction "1_1") (pintype "passive"))
      (node (ref "R15") (pin "1") (pinfunction "1_1") (pintype "passive"))
      (node (ref "U5") (pin "7") (pinfunction "QH_7") (pintype "passive"))
    )
    (net (code "29") (name "/I2S_BCK") (class "Default")
      (node (ref "J1") (pin "10") (pinfunction "10_10") (pintype "passive"))
      (node (ref "U1") (pin "11") (pinfunction "IO26_11") (pintype "passive"))
      (node (ref "U4") (pin "11") (pinfunction "SHCP_11") (pintype "passive"))
      (node (ref "U5") (pin "11") (pinfunction "SHCP_11") (pintype "passive"))
      (node (ref "U6") (pin "11") (pinfunction "SHCP_11") (pintype "passive"))
    )
    (net (code "30") (name "/I2S_DATA") (class "Default")
      (node (ref "J1") (pin "11") (pinfunction "11_11") (pintype "passive"))
      (node (ref "U1") (pin "12") (pinfunction "IO27_12") (pintype "passive"))
      (node (ref "U4") (pin "14") (pinfunction "DS_14") (pintype "passive"))
    )
    (net (code "31") (name "/I2S_WS") (class "Default")
      (node (ref "J1") (pin "9") (pinfunction "9_9") (pintype "passive"))
      (node (ref "U1") (pin "10") (pinfunction "IO25_10") (pintype "passive"))
      (node (ref "U4") (pin "12") (pinfunction "STCP_12") (pintype "passive"))
      (node (ref "U5") (pin "12") (pinfunction "STCP_12") (pintype "passive"))
      (node (ref "U6") (pin "12") (pinfunction "STCP_12") (pintype "passive"))
    )
    (net (code "32") (name "/IO0") (class "Default")
      (node (ref "BOOT1") (pin "1") (pinfunction "1_1") (pintype "passive"))
      (node (ref "J2") (pin "14") (pinfunction "14_14") (pintype "passive"))
      (node (ref "Q9") (pin "3") (pinfunction "C_3") (pintype "passive"))
      (node (ref "R34") (pin "1") (pinfunction "1_1") (pintype "passive"))
      (node (ref "U1") (pin "25") (pinfunction "IO0_25") (pintype "passive"))
    )
    (net (code "33") (name "/IO2") (class "Default")
      (node (ref "J2") (pin "15") (pinfunction "15_15") (pintype "passive"))
      (node (ref "JP5") (pin "1") (pinfunction "1_1") (pintype "passive"))
      (node (ref "R2") (pin "1") (pinfunction "1_1") (pintype "passive"))
      (node (ref "R26") (pin "1") (pinfunction "1_1") (pintype "passive"))
      (node (ref "U1") (pin "24") (pinfunction "IO2_24") (pintype "passive"))
    )
    (net (code "34") (name "/IO4") (class "Default")
      (node (ref "J2") (pin "13") (pinfunction "13_13") (pintype "passive"))
      (node (ref "U1") (pin "26") (pinfunction "IO4_26") (pintype "passive"))
    )
    (net (code "35") (name "/IO5") (class "Default")
      (node (ref "J2") (pin "10") (pinfunction "10_10") (pintype "passive"))
      (node (ref "P4") (pin "12") (pinfunction "12_12") (pintype "passive"))
      (node (ref "U1") (pin "29") (pinfunction "IO5_29") (pintype "passive"))
    )
    (net (code "36") (name "/IO15") (class "Default")
      (node (ref "J2") (pin "16") (pinfunction "16_16") (pintype "passive"))
      (node (ref "JP6") (pin "1") (pinfunction "1_1") (pintype "passive"))
      (node (ref "R27") (pin "1") (pinfunction "1_1") (pintype "passive"))
      (node (ref "U1") (pin "23") (pinfunction "IO15_23") (pintype "passive"))
    )
    (net (code "37") (name "/IO16") (class "Default")
      (node (ref "J2") (pin "12") (pinfunction "12_12") (pintype "passive"))
      (node (ref "U1") (pin "27") (pinfunction "IO16_27") (pintype "passive"))
    )
    (net (code "38") (name "/IO17") (class "Default")
      (node (ref "J2") (pin "11") (pinfunction "11_11") (pintype "passive"))
      (node (ref "U1") (pin "28") (pinfunction "IO17_28") (pintype "passive"))
    )
    (net (code "39") (name "/IO18") (class "Default")
      (node (ref "J2") (pin "9") (pinfunction "9_9") (pintype "passive"))
      (node (ref "P4") (pin "14") (pinfunction "14_14") (pintype "passive"))
      (node (ref "U1") (pin "30") (pinfunction "IO18_30") (pintype "passive"))
    )
    (net (code "40") (name "/IO19") (class "Default")
      (node (ref "J2") (pin "8") (pinfunction "8_8") (pintype "passive"))
      (node (ref "P4") (pin "13") (pinfunction "13_13") (pintype "passive"))
      (node (ref "U1") (pin "31") (pinfunction "IO19_31") (pintype "passive"))
    )
    (net (code "41") (name "/IO21") (class "Default")
      (node (ref "J2") (pin "6") (pinfunction "6_6") (pintype "passive"))
      (node (ref "P4") (pin "4") (pinfunction "4_4") (pintype "passive"))
      (node (ref "U1") (pin "33") (pinfunction "IO21_33") (pintype "passive"))
    )
    (net (code "42") (name "/IO22") (class "Default")
      (node (ref "J2") (pin "3") (pinfunction "3_3") (pintype "passive"))
      (node (ref "P4") (pin "6") (pinfunction "6_6") (pintype "passive"))
      (node (ref "U1") (pin "36") (pinfunction "IO22_36") (pintype "passive"))
    )
    (net (code "43") (name "/IO23") (class "Default")
      (node (ref "J2") (pin "2") (pinfunction "2_2") (pintype "passive"))
      (node (ref "P4") (pin "10") (pinfunction "10_10") (pintype "passive"))
      (node (ref "U1") (pin "37") (pinfunction "IO23_37") (pintype "passive"))
    )
    (net (code "44") (name "/IO32") (class "Default")
      (node (ref "J1") (pin "7") (pinfunction "7_7") (pintype "passive"))
      (node (ref "JP2") (pin "1") (pinfunction "1_1") (pintype "passive"))
      (node (ref "R21") (pin "1") (pinfunction "1_1") (pintype "passive"))
      (node (ref "U1") (pin "8") (pinfunction "IO32_8") (pintype "passive"))
    )
    (net (code "45") (name "/IO33") (class "Default")
      (node (ref "J1") (pin "8") (pinfunction "8_8") (pintype "passive"))
      (node (ref "JP4") (pin "1") (pinfunction "1_1") (pintype "passive"))
      (node (ref "R24") (pin "1") (pinfunction "1_1") (pintype "passive"))
      (node (ref "U1") (pin "9") (pinfunction "IO33_9") (pintype "passive"))
    )
    (net (code "46") (name "/IO34") (class "Default")
      (node (ref "J1") (pin "5") (pinfunction "5_5") (pintype "passive"))
      (node (ref "U1") (pin "6") (pinfunction "IO34_6") (pintype "passive"))
    )
    (net (code "47") (name "/IO35") (class "Default")
      (node (ref "J1") (pin "6") (pinfunction "6_6") (pintype "passive"))
      (node (ref "JP1") (pin "1") (pinfunction "1_1") (pintype "passive"))
      (node (ref "R18") (pin "1") (pinfunction "1_1") (pintype "passive"))
      (node (ref "U1") (pin "7") (pinfunction "IO35_7") (pintype "passive"))
    )
    (net (code "48") (name "/LCD_D5") (class "Default")
      (node (ref "U6") (pin "5") (pinfunction "QF_5") (pintype "passive"))
    )
    (net (code "49") (name "/LCD_D6") (class "Default")
      (node (ref "U6") (pin "6") (pinfunction "QG_6") (pintype "passive"))
    )
    (net (code "50") (name "/LCD_D7") (class "Default")
      (node (ref "U6") (pin "7") (pinfunction "QH_7") (pintype "passive"))
    )
    (net (code "51") (name "/MISO13") (class "Default")
      (node (ref "P7") (pin "13") (pinfunction "13_13") (pintype "passive"))
      (node (ref "R16") (pin "2") (pinfunction "2_2") (pintype "passive"))
      (node (ref "U3") (pin "7") (pinfunction "DATA0_7") (pintype "passive"))
    )
    (net (code "52") (name "/MOSI10") (class "Default")
      (node (ref "P7") (pin "10") (pinfunction "10_10") (pintype "passive"))
      (node (ref "R20") (pin "2") (pinfunction "2_2") (pintype "passive"))
      (node (ref "U3") (pin "3") (pinfunction "CMD_3") (pintype "passive"))
    )
    (net (code "53") (name "/RST8") (class "Default")
      (node (ref "P7") (pin "8") (pinfunction "8_8") (pintype "passive"))
      (node (ref "REST1") (pin "1") (pinfunction "1_1") (pintype "passive"))
    )
    (net (code "54") (name "/RTS") (class "Default")
      (node (ref "Q8") (pin "2") (pinfunction "E_2") (pintype "passive"))
      (node (ref "R29") (pin "2") (pinfunction "2_2") (pintype "passive"))
      (node (ref "U8") (pin "14") (pinfunction "RTS#_14") (pintype "passive"))
    )
    (net (code "55") (name "/RXD") (class "Default")
      (node (ref "J2") (pin "5") (pinfunction "5_5") (pintype "passive"))
      (node (ref "LED_TXD1") (pin "2") (pinfunction "2_2") (pintype "passive"))
      (node (ref "U1") (pin "34") (pinfunction "RXD0_34") (pintype "passive"))
      (node (ref "U8") (pin "2") (pinfunction "TXD_2") (pintype "passive"))
    )
    (net (code "56") (name "/SCK14") (class "Default")
      (node (ref "P7") (pin "14") (pinfunction "14_14") (pintype "passive"))
      (node (ref "R17") (pin "2") (pinfunction "2_2") (pintype "passive"))
      (node (ref "U3") (pin "5") (pinfunction "CLK_5") (pintype "passive"))
    )
    (net (code "57") (name "/SCL6") (class "Default")
      (node (ref "P6") (pin "3") (pinfunction "3_3") (pintype "passive"))
      (node (ref "P7") (pin "6") (pinfunction "6_6") (pintype "passive"))
    )
    (net (code "58") (name "/SD0") (class "Default")
      (node (ref "J2") (pin "18") (pinfunction "18_18") (pintype "passive"))
      (node (ref "U1") (pin "21") (pinfunction "SD0_21") (pintype "passive"))
    )
    (net (code "59") (name "/SD1") (class "Default")
      (node (ref "J2") (pin "17") (pinfunction "17_17") (pintype "passive"))
      (node (ref "U1") (pin "22") (pinfunction "SD1_22") (pintype "passive"))
    )
    (net (code "60") (name "/SD2") (class "Default")
      (node (ref "J1") (pin "16") (pinfunction "16_16") (pintype "passive"))
      (node (ref "U1") (pin "17") (pinfunction "SD2_17") (pintype "passive"))
    )
    (net (code "61") (name "/SD3") (class "Default")
      (node (ref "J1") (pin "17") (pinfunction "17_17") (pintype "passive"))
      (node (ref "U1") (pin "18") (pinfunction "SD3_18") (pintype "passive"))
    )
    (net (code "62") (name "/SDA4") (class "Default")
      (node (ref "P6") (pin "4") (pinfunction "4_4") (pintype "passive"))
      (node (ref "P7") (pin "4") (pinfunction "4_4") (pintype "passive"))
    )
    (net (code "63") (name "/SDSS12") (class "Default")
      (node (ref "P7") (pin "12") (pinfunction "12_12") (pintype "passive"))
      (node (ref "R23") (pin "2") (pinfunction "2_2") (pintype "passive"))
      (node (ref "U3") (pin "2") (pinfunction "DATA3_2") (pintype "passive"))
    )
    (net (code "64") (name "/SVN") (class "Default")
      (node (ref "C4") (pin "1") (pinfunction "1_1") (pintype "passive"))
      (node (ref "J1") (pin "4") (pinfunction "4_4") (pintype "passive"))
      (node (ref "P3") (pin "1") (pinfunction "1_1") (pintype "passive"))
      (node (ref "R4") (pin "1") (pinfunction "1_1") (pintype "passive"))
      (node (ref "U1") (pin "5") (pinfunction "SENSOR_VN_5") (pintype "passive"))
    )
    (net (code "65") (name "/SVP") (class "Default")
      (node (ref "C3") (pin "1") (pinfunction "1_1") (pintype "passive"))
      (node (ref "J1") (pin "3") (pinfunction "3_3") (pintype "passive"))
      (node (ref "P2") (pin "1") (pinfunction "1_1") (pintype "passive"))
      (node (ref "R3") (pin "2") (pinfunction "2_2") (pintype "passive"))
      (node (ref "U1") (pin "4") (pinfunction "SENSOR_VP_4") (pintype "passive"))
    )
    (net (code "66") (name "/TXD") (class "Default")
      (node (ref "J2") (pin "4") (pinfunction "4_4") (pintype "passive"))
      (node (ref "LED_RXD1") (pin "2") (pinfunction "2_2") (pintype "passive"))
      (node (ref "U1") (pin "35") (pinfunction "TXD0_35") (pintype "passive"))
      (node (ref "U8") (pin "3") (pinfunction "RXD_3") (pintype "passive"))
    )
    (net (code "67") (name "/X.DIR") (class "Default")
      (node (ref "P16") (pin "8") (pinfunction "8_8") (pintype "passive"))
      (node (ref "U4") (pin "2") (pinfunction "QC_2") (pintype "passive"))
    )
    (net (code "68") (name "/X.ENABLE") (class "Default")
      (node (ref "P16") (pin "1") (pinfunction "1_1") (pintype "passive"))
      (node (ref "U4") (pin "15") (pinfunction "Q0_15") (pintype "passive"))
    )
    (net (code "69") (name "/X.STP") (class "Default")
      (node (ref "P16") (pin "7") (pinfunction "7_7") (pintype "passive"))
      (node (ref "U4") (pin "1") (pinfunction "QB_1") (pintype "passive"))
    )
    (net (code "70") (name "/Y.DIR") (class "Default")
      (node (ref "P17") (pin "8") (pinfunction "8_8") (pintype "passive"))
      (node (ref "U4") (pin "5") (pinfunction "QF_5") (pintype "passive"))
    )
    (net (code "71") (name "/Y.ENABLE") (class "Default")
      (node (ref "P17") (pin "1") (pinfunction "1_1") (pintype "passive"))
      (node (ref "U4") (pin "3") (pinfunction "QD_3") (pintype "passive"))
    )
    (net (code "72") (name "/Y.STP") (class "Default")
      (node (ref "P17") (pin "7") (pinfunction "7_7") (pintype "passive"))
      (node (ref "U4") (pin "4") (pinfunction "QE_4") (pintype "passive"))
    )
    (net (code "73") (name "/Z.DIR") (class "Default")
      (node (ref "P18") (pin "8") (pinfunction "8_8") (pintype "passive"))
      (node (ref "U5") (pin "15") (pinfunction "Q0_15") (pintype "passive"))
    )
    (net (code "74") (name "/Z.ENABLE") (class "Default")
      (node (ref "P18") (pin "1") (pinfunction "1_1") (pintype "passive"))
      (node (ref "U4") (pin "6") (pinfunction "QG_6") (pintype "passive"))
    )
    (net (code "75") (name "/Z.STP") (class "Default")
      (node (ref "P18") (pin "7") (pinfunction "7_7") (pintype "passive"))
      (node (ref "U4") (pin "7") (pinfunction "QH_7") (pintype "passive"))
    )
    (net (code "76") (name "/gg") (class "Default")
      (node (ref "P6") (pin "1") (pinfunction "1_1") (pintype "passive"))
      (node (ref "P7") (pin "1") (pinfunction "1_1") (pintype "passive"))
      (node (ref "Q5") (pin "2") (pinfunction "E_2") (pintype "passive"))
      (node (ref "R30") (pin "2") (pinfunction "2_2") (pintype "passive"))
      (node (ref "REST1") (pin "2") (pinfunction "2_2") (pintype "passive"))
      (node (ref "SW1") (pin "6") (pinfunction "6_6") (pintype "passive"))
      (node (ref "SW1") (pin "7") (pinfunction "7_7") (pintype "passive"))
      (node (ref "SW1") (pin "C") (pinfunction "C_C") (pintype "passive"))
      (node (ref "SW1") (pin "D") (pinfunction "D_D") (pintype "passive"))
      (node (ref "U3") (pin "10") (pinfunction "GND_10") (pintype "passive"))
      (node (ref "U3") (pin "11") (pinfunction "GND_11") (pintype "passive"))
      (node (ref "U3") (pin "12") (pinfunction "GND_12") (pintype "passive"))
      (node (ref "U3") (pin "13") (pinfunction "GND_13") (pintype "passive"))
      (node (ref "U3") (pin "6") (pinfunction "VSS_6") (pintype "passive"))
    )
    (net (code "77") (name "GND") (class "Default")
      (node (ref "BOOT1") (pin "2") (pinfunction "2_2") (pintype "passive"))
      (node (ref "C1") (pin "2") (pinfunction "2_2") (pintype "passive"))
      (node (ref "C10") (pin "1") (pinfunction "1_1") (pintype "passive"))
      (node (ref "C11") (pin "2") (pinfunction "2_2") (pintype "passive"))
      (node (ref "C12") (pin "2") (pinfunction "2_2") (pintype "passive"))
      (node (ref "C13") (pin "2") (pinfunction "2_2") (pintype "passive"))
      (node (ref "C14") (pin "2") (pinfunction "2_2") (pintype "passive"))
      (node (ref "C15") (pin "2") (pinfunction "2_2") (pintype "passive"))
      (node (ref "C2") (pin "2") (pinfunction "2_2") (pintype "passive"))
      (node (ref "C3") (pin "2") (pinfunction "2_2") (pintype "passive"))
      (node (ref "C4") (pin "2") (pinfunction "2_2") (pintype "passive"))
      (node (ref "C5") (pin "2") (pinfunction "2_2") (pintype "passive"))
      (node (ref "C6") (pin "1") (pinfunction "1_1") (pintype "passive"))
      (node (ref "C7") (pin "2") (pinfunction "2_2") (pintype "passive"))
      (node (ref "C8") (pin "1") (pinfunction "1_1") (pintype "passive"))
      (node (ref "C9") (pin "1") (pinfunction "1_1") (pintype "passive"))
      (node (ref "D1") (pin "1") (pinfunction "A_1") (pintype "passive"))
      (node (ref "D2") (pin "2") (pinfunction "K_2") (pintype "passive"))
      (node (ref "D3") (pin "1") (pinfunction "A_1") (pintype "passive"))
      (node (ref "D4") (pin "2") (pinfunction "K_2") (pintype "passive"))
      (node (ref "D6") (pin "2") (pinfunction "K_2") (pintype "passive"))
      (node (ref "J1") (pin "14") (pinfunction "14_14") (pintype "passive"))
      (node (ref "J2") (pin "1") (pinfunction "1_1") (pintype "passive"))
      (node (ref "J2") (pin "7") (pinfunction "7_7") (pintype "passive"))
      (node (ref "JP1") (pin "2") (pinfunction "2_2") (pintype "passive"))
      (node (ref "JP2") (pin "2") (pinfunction "2_2") (pintype "passive"))
      (node (ref "JP4") (pin "2") (pinfunction "2_2") (pintype "passive"))
      (node (ref "JP5") (pin "2") (pinfunction "2_2") (pintype "passive"))
      (node (ref "JP6") (pin "2") (pinfunction "2_2") (pintype "passive"))
      (node (ref "P16") (pin "10") (pinfunction "10_10") (pintype "passive"))
      (node (ref "P16") (pin "16") (pinfunction "16_16") (pintype "passive"))
      (node (ref "P17") (pin "10") (pinfunction "10_10") (pintype "passive"))
      (node (ref "P17") (pin "16") (pinfunction "16_16") (pintype "passive"))
      (node (ref "P18") (pin "10") (pinfunction "10_10") (pintype "passive"))
      (node (ref "P18") (pin "16") (pinfunction "16_16") (pintype "passive"))
      (node (ref "P19") (pin "10") (pinfunction "10_10") (pintype "passive"))
      (node (ref "P19") (pin "16") (pinfunction "16_16") (pintype "passive"))
      (node (ref "P2") (pin "2") (pinfunction "2_2") (pintype "passive"))
      (node (ref "P20") (pin "10") (pinfunction "10_10") (pintype "passive"))
      (node (ref "P20") (pin "16") (pinfunction "16_16") (pintype "passive"))
      (node (ref "P3") (pin "2") (pinfunction "2_2") (pintype "passive"))
      (node (ref "P4") (pin "1") (pinfunction "1_1") (pintype "passive"))
      (node (ref "P9") (pin "2") (pinfunction "2_2") (pintype "passive"))
      (node (ref "Q2") (pin "3") (pinfunction "S_3") (pintype "passive"))
      (node (ref "Q4") (pin "3") (pinfunction "S_3") (pintype "passive"))
      (node (ref "Q7") (pin "3") (pinfunction "S_3") (pintype "passive"))
      (node (ref "R10") (pin "1") (pinfunction "1_1") (pintype "passive"))
      (node (ref "R19") (pin "1") (pinfunction "1_1") (pintype "passive"))
      (node (ref "R31") (pin "1") (pinfunction "1_1") (pintype "passive"))
      (node (ref "R32") (pin "1") (pinfunction "1_1") (pintype "passive"))
      (node (ref "R5") (pin "1") (pinfunction "1_1") (pintype "passive"))
      (node (ref "U1") (pin "1") (pinfunction "GND_1") (pintype "passive"))
      (node (ref "U1") (pin "15") (pinfunction "GND_15") (pintype "passive"))
      (node (ref "U1") (pin "38") (pinfunction "GND_38") (pintype "passive"))
      (node (ref "U1") (pin "39") (pinfunction "GND_39") (pintype "passive"))
      (node (ref "U2") (pin "4") (pinfunction "ON/OFF_4") (pintype "passive"))
      (node (ref "U2") (pin "5") (pinfunction "GND_5") (pintype "passive"))
      (node (ref "U2") (pin "6") (pinfunction "GND_6") (pintype "passive"))
      (node (ref "U2") (pin "7") (pinfunction "GND_7") (pintype "passive"))
      (node (ref "U2") (pin "8") (pinfunction "GND_8") (pintype "passive"))
      (node (ref "U4") (pin "13") (pinfunction "OE_13") (pintype "passive"))
      (node (ref "U4") (pin "8") (pinfunction "GND_8") (pintype "passive"))
      (node (ref "U5") (pin "13") (pinfunction "OE_13") (pintype "passive"))
      (node (ref "U5") (pin "8") (pinfunction "GND_8") (pintype "passive"))
      (node (ref "U6") (pin "13") (pinfunction "OE_13") (pintype "passive"))
      (node (ref "U6") (pin "8") (pinfunction "GND_8") (pintype "passive"))
      (node (ref "U7") (pin "1") (pinfunction "ADJ(GND)_1") (pintype "passive"))
      (node (ref "U8") (pin "1") (pinfunction "GND_1") (pintype "passive"))
      (node (ref "USB C1") (pin "1") (pinfunction "SHELL_1") (pintype "passive"))
      (node (ref "USB C1") (pin "2") (pinfunction "SHELL_2") (pintype "passive"))
      (node (ref "USB C1") (pin "3") (pinfunction "SHELL_3") (pintype "passive"))
      (node (ref "USB C1") (pin "4") (pinfunction "SHELL_4") (pintype "passive"))
      (node (ref "USB C1") (pin "A1B12") (pinfunction "GND_A1B12") (pintype "passive"))
      (node (ref "USB C1") (pin "B1A12") (pinfunction "GND_B1A12") (pintype "passive"))
      (node (ref "USB-LED1") (pin "2") (pinfunction "2_2") (pintype "passive"))
    )
    (net (code "78") (name "Net-(D2-A)") (class "Default")
      (node (ref "D2") (pin "1") (pinfunction "A_1") (pintype "passive"))
      (node (ref "R7") (pin "2") (pinfunction "2_2") (pintype "passive"))
    )
    (net (code "79") (name "Net-(D3-K)") (class "Default")
      (node (ref "D3") (pin "2") (pinfunction "K_2") (pintype "passive"))
      (node (ref "L1") (pin "1") (pinfunction "1_1") (pintype "passive"))
      (node (ref "U2") (pin "2") (pinfunction "OUTPUT_2") (pintype "passive"))
    )
    (net (code "80") (name "Net-(D4-A)") (class "Default")
      (node (ref "D4") (pin "1") (pinfunction "A_1") (pintype "passive"))
      (node (ref "R15") (pin "2") (pinfunction "2_2") (pintype "passive"))
    )
    (net (code "81") (name "Net-(D6-A)") (class "Default")
      (node (ref "D6") (pin "1") (pinfunction "A_1") (pintype "passive"))
      (node (ref "R25") (pin "2") (pinfunction "2_2") (pintype "passive"))
    )
    (net (code "82") (name "Net-(F1-Pad1)") (class "Default")
      (node (ref "F1") (pin "1") (pinfunction "1_1") (pintype "passive"))
      (node (ref "F2") (pin "1") (pinfunction "1_1") (pintype "passive"))
      (node (ref "P9") (pin "1") (pinfunction "1_1") (pintype "passive"))
    )
    (net (code "83") (name "Net-(LED1-Pad2)") (class "Default")
      (node (ref "LED1") (pin "2") (pinfunction "2_2") (pintype "passive"))
      (node (ref "R30") (pin "1") (pinfunction "1_1") (pintype "passive"))
    )
    (net (code "84") (name "Net-(LED_RXD1-Pad1)") (class "Default")
      (node (ref "LED_RXD1") (pin "1") (pinfunction "1_1") (pintype "passive"))
      (node (ref "LED_TXD1") (pin "1") (pinfunction "1_1") (pintype "passive"))
      (node (ref "R8") (pin "2") (pinfunction "2_2") (pintype "passive"))
    )
    (net (code "85") (name "Net-(P11-Pad4)") (class "Default")
      (node (ref "P11") (pin "4") (pinfunction "4_4") (pintype "passive"))
      (node (ref "P16") (pin "2") (pinfunction "2_2") (pintype "passive"))
    )
    (net (code "86") (name "Net-(P11-Pad5)") (class "Default")
      (node (ref "P11") (pin "5") (pinfunction "5_5") (pintype "passive"))
      (node (ref "P16") (pin "3") (pinfunction "3_3") (pintype "passive"))
    )
    (net (code "87") (name "Net-(P11-Pad6)") (class "Default")
      (node (ref "P11") (pin "6") (pinfunction "6_6") (pintype "passive"))
      (node (ref "P16") (pin "4") (pinfunction "4_4") (pintype "passive"))
    )
    (net (code "88") (name "Net-(P12-Pad4)") (class "Default")
      (node (ref "P12") (pin "4") (pinfunction "4_4") (pintype "passive"))
      (node (ref "P17") (pin "2") (pinfunction "2_2") (pintype "passive"))
    )
    (net (code "89") (name "Net-(P12-Pad5)") (class "Default")
      (node (ref "P12") (pin "5") (pinfunction "5_5") (pintype "passive"))
      (node (ref "P17") (pin "3") (pinfunction "3_3") (pintype "passive"))
    )
    (net (code "90") (name "Net-(P12-Pad6)") (class "Default")
      (node (ref "P12") (pin "6") (pinfunction "6_6") (pintype "passive"))
      (node (ref "P17") (pin "4") (pinfunction "4_4") (pintype "passive"))
    )
    (net (code "91") (name "Net-(P13-Pad4)") (class "Default")
      (node (ref "P13") (pin "4") (pinfunction "4_4") (pintype "passive"))
      (node (ref "P18") (pin "2") (pinfunction "2_2") (pintype "passive"))
    )
    (net (code "92") (name "Net-(P13-Pad5)") (class "Default")
      (node (ref "P13") (pin "5") (pinfunction "5_5") (pintype "passive"))
      (node (ref "P18") (pin "3") (pinfunction "3_3") (pintype "passive"))
    )
    (net (code "93") (name "Net-(P13-Pad6)") (class "Default")
      (node (ref "P13") (pin "6") (pinfunction "6_6") (pintype "passive"))
      (node (ref "P18") (pin "4") (pinfunction "4_4") (pintype "passive"))
    )
    (net (code "94") (name "Net-(P14-Pad4)") (class "Default")
      (node (ref "P14") (pin "4") (pinfunction "4_4") (pintype "passive"))
      (node (ref "P19") (pin "2") (pinfunction "2_2") (pintype "passive"))
    )
    (net (code "95") (name "Net-(P14-Pad5)") (class "Default")
      (node (ref "P14") (pin "5") (pinfunction "5_5") (pintype "passive"))
      (node (ref "P19") (pin "3") (pinfunction "3_3") (pintype "passive"))
    )
    (net (code "96") (name "Net-(P14-Pad6)") (class "Default")
      (node (ref "P14") (pin "6") (pinfunction "6_6") (pintype "passive"))
      (node (ref "P19") (pin "4") (pinfunction "4_4") (pintype "passive"))
    )
    (net (code "97") (name "Net-(P15-Pad4)") (class "Default")
      (node (ref "P15") (pin "4") (pinfunction "4_4") (pintype "passive"))
      (node (ref "P20") (pin "2") (pinfunction "2_2") (pintype "passive"))
    )
    (net (code "98") (name "Net-(P15-Pad5)") (class "Default")
      (node (ref "P15") (pin "5") (pinfunction "5_5") (pintype "passive"))
      (node (ref "P20") (pin "3") (pinfunction "3_3") (pintype "passive"))
    )
    (net (code "99") (name "Net-(P15-Pad6)") (class "Default")
      (node (ref "P15") (pin "6") (pinfunction "6_6") (pintype "passive"))
      (node (ref "P20") (pin "4") (pinfunction "4_4") (pintype "passive"))
    )
    (net (code "100") (name "Net-(P16-Pad5)") (class "Default")
      (node (ref "P16") (pin "5") (pinfunction "5_5") (pintype "passive"))
      (node (ref "P16") (pin "6") (pinfunction "6_6") (pintype "passive"))
    )
    (net (code "101") (name "Net-(P16-Pad11)") (class "Default")
      (node (ref "P16") (pin "11") (pinfunction "11_11") (pintype "passive"))
      (node (ref "P21") (pin "1") (pinfunction "1_1") (pintype "passive"))
    )
    (net (code "102") (name "Net-(P16-Pad12)") (class "Default")
      (node (ref "P16") (pin "12") (pinfunction "12_12") (pintype "passive"))
      (node (ref "P21") (pin "2") (pinfunction "2_2") (pintype "passive"))
    )
    (net (code "103") (name "Net-(P16-Pad13)") (class "Default")
      (node (ref "P16") (pin "13") (pinfunction "13_13") (pintype "passive"))
      (node (ref "P21") (pin "3") (pinfunction "3_3") (pintype "passive"))
    )
    (net (code "104") (name "Net-(P16-Pad14)") (class "Default")
      (node (ref "P16") (pin "14") (pinfunction "14_14") (pintype "passive"))
      (node (ref "P21") (pin "4") (pinfunction "4_4") (pintype "passive"))
    )
    (net (code "105") (name "Net-(P17-Pad5)") (class "Default")
      (node (ref "P17") (pin "5") (pinfunction "5_5") (pintype "passive"))
      (node (ref "P17") (pin "6") (pinfunction "6_6") (pintype "passive"))
    )
    (net (code "106") (name "Net-(P17-Pad11)") (class "Default")
      (node (ref "P17") (pin "11") (pinfunction "11_11") (pintype "passive"))
      (node (ref "P22") (pin "1") (pinfunction "1_1") (pintype "passive"))
    )
    (net (code "107") (name "Net-(P17-Pad12)") (class "Default")
      (node (ref "P17") (pin "12") (pinfunction "12_12") (pintype "passive"))
      (node (ref "P22") (pin "2") (pinfunction "2_2") (pintype "passive"))
    )
    (net (code "108") (name "Net-(P17-Pad13)") (class "Default")
      (node (ref "P17") (pin "13") (pinfunction "13_13") (pintype "passive"))
      (node (ref "P22") (pin "3") (pinfunction "3_3") (pintype "passive"))
    )
    (net (code "109") (name "Net-(P17-Pad14)") (class "Default")
      (node (ref "P17") (pin "14") (pinfunction "14_14") (pintype "passive"))
      (node (ref "P22") (pin "4") (pinfunction "4_4") (pintype "passive"))
    )
    (net (code "110") (name "Net-(P18-Pad5)") (class "Default")
      (node (ref "P18") (pin "5") (pinfunction "5_5") (pintype "passive"))
      (node (ref "P18") (pin "6") (pinfunction "6_6") (pintype "passive"))
    )
    (net (code "111") (name "Net-(P18-Pad11)") (class "Default")
      (node (ref "P18") (pin "11") (pinfunction "11_11") (pintype "passive"))
      (node (ref "P25") (pin "1") (pinfunction "1_1") (pintype "passive"))
      (node (ref "P26") (pin "1") (pinfunction "1_1") (pintype "passive"))
    )
    (net (code "112") (name "Net-(P18-Pad12)") (class "Default")
      (node (ref "P18") (pin "12") (pinfunction "12_12") (pintype "passive"))
      (node (ref "P25") (pin "2") (pinfunction "2_2") (pintype "passive"))
      (node (ref "P26") (pin "2") (pinfunction "2_2") (pintype "passive"))
    )
    (net (code "113") (name "Net-(P18-Pad13)") (class "Default")
      (node (ref "P18") (pin "13") (pinfunction "13_13") (pintype "passive"))
      (node (ref "P25") (pin "3") (pinfunction "3_3") (pintype "passive"))
      (node (ref "P26") (pin "3") (pinfunction "3_3") (pintype "passive"))
    )
    (net (code "114") (name "Net-(P18-Pad14)") (class "Default")
      (node (ref "P18") (pin "14") (pinfunction "14_14") (pintype "passive"))
      (node (ref "P25") (pin "4") (pinfunction "4_4") (pintype "passive"))
      (node (ref "P26") (pin "4") (pinfunction "4_4") (pintype "passive"))
    )
    (net (code "115") (name "Net-(P19-Pad5)") (class "Default")
      (node (ref "P19") (pin "5") (pinfunction "5_5") (pintype "passive"))
      (node (ref "P19") (pin "6") (pinfunction "6_6") (pintype "passive"))
    )
    (net (code "116") (name "Net-(P19-Pad11)") (class "Default")
      (node (ref "P19") (pin "11") (pinfunction "11_11") (pintype "passive"))
      (node (ref "P23") (pin "1") (pinfunction "1_1") (pintype "passive"))
    )
    (net (code "117") (name "Net-(P19-Pad12)") (class "Default")
      (node (ref "P19") (pin "12") (pinfunction "12_12") (pintype "passive"))
      (node (ref "P23") (pin "2") (pinfunction "2_2") (pintype "passive"))
    )
    (net (code "118") (name "Net-(P19-Pad13)") (class "Default")
      (node (ref "P19") (pin "13") (pinfunction "13_13") (pintype "passive"))
      (node (ref "P23") (pin "3") (pinfunction "3_3") (pintype "passive"))
    )
    (net (code "119") (name "Net-(P19-Pad14)") (class "Default")
      (node (ref "P19") (pin "14") (pinfunction "14_14") (pintype "passive"))
      (node (ref "P23") (pin "4") (pinfunction "4_4") (pintype "passive"))
    )
    (net (code "120") (name "Net-(P20-Pad5)") (class "Default")
      (node (ref "P20") (pin "5") (pinfunction "5_5") (pintype "passive"))
      (node (ref "P20") (pin "6") (pinfunction "6_6") (pintype "passive"))
    )
    (net (code "121") (name "Net-(P20-Pad11)") (class "Default")
      (node (ref "P20") (pin "11") (pinfunction "11_11") (pintype "passive"))
      (node (ref "P24") (pin "1") (pinfunction "1_1") (pintype "passive"))
    )
    (net (code "122") (name "Net-(P20-Pad12)") (class "Default")
      (node (ref "P20") (pin "12") (pinfunction "12_12") (pintype "passive"))
      (node (ref "P24") (pin "2") (pinfunction "2_2") (pintype "passive"))
    )
    (net (code "123") (name "Net-(P20-Pad13)") (class "Default")
      (node (ref "P20") (pin "13") (pinfunction "13_13") (pintype "passive"))
      (node (ref "P24") (pin "3") (pinfunction "3_3") (pintype "passive"))
    )
    (net (code "124") (name "Net-(P20-Pad14)") (class "Default")
      (node (ref "P20") (pin "14") (pinfunction "14_14") (pintype "passive"))
      (node (ref "P24") (pin "4") (pinfunction "4_4") (pintype "passive"))
    )
    (net (code "125") (name "Net-(Q1-D)") (class "Default")
      (node (ref "P1") (pin "2") (pinfunction "2_2") (pintype "passive"))
      (node (ref "Q1") (pin "1") (pinfunction "D_1") (pintype "passive"))
      (node (ref "Q2") (pin "1") (pinfunction "D_1") (pintype "passive"))
    )
    (net (code "126") (name "Net-(Q2-G)") (class "Default")
      (node (ref "Q2") (pin "2") (pinfunction "G_2") (pintype "passive"))
      (node (ref "R5") (pin "2") (pinfunction "2_2") (pintype "passive"))
      (node (ref "R6") (pin "2") (pinfunction "2_2") (pintype "passive"))
    )
    (net (code "127") (name "Net-(Q3-D)") (class "Default")
      (node (ref "P5") (pin "2") (pinfunction "2_2") (pintype "passive"))
      (node (ref "Q3") (pin "1") (pinfunction "D_1") (pintype "passive"))
      (node (ref "Q4") (pin "1") (pinfunction "D_1") (pintype "passive"))
    )
    (net (code "128") (name "Net-(Q4-G)") (class "Default")
      (node (ref "Q4") (pin "2") (pinfunction "G_2") (pintype "passive"))
      (node (ref "R10") (pin "2") (pinfunction "2_2") (pintype "passive"))
      (node (ref "R13") (pin "2") (pinfunction "2_2") (pintype "passive"))
    )
    (net (code "129") (name "Net-(Q5-B)") (class "Default")
      (node (ref "Q5") (pin "1") (pinfunction "B_1") (pintype "passive"))
      (node (ref "R12") (pin "2") (pinfunction "2_2") (pintype "passive"))
    )
    (net (code "130") (name "Net-(Q5-C)") (class "Default")
      (node (ref "Q5") (pin "3") (pinfunction "C_3") (pintype "passive"))
      (node (ref "d5") (pin "2") (pinfunction "2_2") (pintype "passive"))
    )
    (net (code "131") (name "Net-(Q6-D)") (class "Default")
      (node (ref "P8") (pin "2") (pinfunction "2_2") (pintype "passive"))
      (node (ref "Q6") (pin "1") (pinfunction "D_1") (pintype "passive"))
      (node (ref "Q7") (pin "1") (pinfunction "D_1") (pintype "passive"))
    )
    (net (code "132") (name "Net-(Q7-G)") (class "Default")
      (node (ref "Q7") (pin "2") (pinfunction "G_2") (pintype "passive"))
      (node (ref "R19") (pin "2") (pinfunction "2_2") (pintype "passive"))
      (node (ref "R22") (pin "2") (pinfunction "2_2") (pintype "passive"))
    )
    (net (code "133") (name "Net-(Q8-B)") (class "Default")
      (node (ref "Q8") (pin "1") (pinfunction "B_1") (pintype "passive"))
      (node (ref "R28") (pin "1") (pinfunction "1_1") (pintype "passive"))
    )
    (net (code "134") (name "Net-(Q9-B)") (class "Default")
      (node (ref "Q9") (pin "1") (pinfunction "B_1") (pintype "passive"))
      (node (ref "R29") (pin "1") (pinfunction "1_1") (pintype "passive"))
    )
    (net (code "135") (name "Net-(R2-Pad2)") (class "Default")
      (node (ref "R2") (pin "2") (pinfunction "2_2") (pintype "passive"))
      (node (ref "USB-LED1") (pin "1") (pinfunction "1_1") (pintype "passive"))
    )
    (net (code "136") (name "Net-(R9-Pad2)") (class "Default")
      (node (ref "R9") (pin "2") (pinfunction "2_2") (pintype "passive"))
      (node (ref "SW1") (pin "A") (pinfunction "A_A") (pintype "passive"))
    )
    (net (code "137") (name "Net-(R11-Pad2)") (class "Default")
      (node (ref "R11") (pin "2") (pinfunction "2_2") (pintype "passive"))
      (node (ref "SW1") (pin "E") (pinfunction "E_E") (pintype "passive"))
    )
    (net (code "138") (name "Net-(R14-Pad1)") (class "Default")
      (node (ref "R14") (pin "1") (pinfunction "1_1") (pintype "passive"))
      (node (ref "SW1") (pin "B") (pinfunction "B_B") (pintype "passive"))
    )
    (net (code "139") (name "Net-(U4-SQH)") (class "Default")
      (node (ref "U4") (pin "9") (pinfunction "SQH_9") (pintype "passive"))
      (node (ref "U5") (pin "14") (pinfunction "DS_14") (pintype "passive"))
    )
    (net (code "140") (name "Net-(U5-SQH)") (class "Default")
      (node (ref "U5") (pin "9") (pinfunction "SQH_9") (pintype "passive"))
      (node (ref "U6") (pin "14") (pinfunction "DS_14") (pintype "passive"))
    )
    (net (code "141") (name "Net-(U8-V3)") (class "Default")
      (node (ref "C8") (pin "2") (pinfunction "2_2") (pintype "passive"))
      (node (ref "U8") (pin "4") (pinfunction "V3_4") (pintype "passive"))
    )
    (net (code "142") (name "Net-(USB C1-CC1)") (class "Default")
      (node (ref "R32") (pin "2") (pinfunction "2_2") (pintype "passive"))
      (node (ref "USB C1") (pin "A5") (pinfunction "CC1_A5") (pintype "passive"))
    )
    (net (code "143") (name "Net-(USB C1-CC2)") (class "Default")
      (node (ref "R31") (pin "2") (pinfunction "2_2") (pintype "passive"))
      (node (ref "USB C1") (pin "B5") (pinfunction "CC2_B5") (pintype "passive"))
    )
    (net (code "144") (name "VBUS") (class "Default")
      (node (ref "D7") (pin "1") (pinfunction "A_1") (pintype "passive"))
      (node (ref "USB C1") (pin "A4B9") (pinfunction "VBUS_A4B9") (pintype "passive"))
      (node (ref "USB C1") (pin "B4A9") (pinfunction "VBUS_B4A9") (pintype "passive"))
    )
    (net (code "145") (name "VCC") (class "Default")
      (node (ref "C11") (pin "1") (pinfunction "1_1") (pintype "passive"))
      (node (ref "C12") (pin "1") (pinfunction "1_1") (pintype "passive"))
      (node (ref "C13") (pin "1") (pinfunction "1_1") (pintype "passive"))
      (node (ref "C14") (pin "1") (pinfunction "1_1") (pintype "passive"))
      (node (ref "C15") (pin "1") (pinfunction "1_1") (pintype "passive"))
      (node (ref "F1") (pin "2") (pinfunction "2_2") (pintype "passive"))
      (node (ref "P1") (pin "1") (pinfunction "1_1") (pintype "passive"))
      (node (ref "P16") (pin "9") (pinfunction "9_9") (pintype "passive"))
      (node (ref "P17") (pin "9") (pinfunction "9_9") (pintype "passive"))
      (node (ref "P18") (pin "9") (pinfunction "9_9") (pintype "passive"))
      (node (ref "P19") (pin "9") (pinfunction "9_9") (pintype "passive"))
      (node (ref "P20") (pin "9") (pinfunction "9_9") (pintype "passive"))
      (node (ref "P5") (pin "1") (pinfunction "1_1") (pintype "passive"))
      (node (ref "P8") (pin "1") (pinfunction "1_1") (pintype "passive"))
    )
    (net (code "146") (name "VCC1") (class "Default")
      (node (ref "C1") (pin "1") (pinfunction "1_1") (pintype "passive"))
      (node (ref "C2") (pin "1") (pinfunction "1_1") (pintype "passive"))
      (node (ref "D1") (pin "2") (pinfunction "K_2") (pintype "passive"))
      (node (ref "F2") (pin "2") (pinfunction "2_2") (pintype "passive"))
      (node (ref "U2") (pin "1") (pinfunction "VIN_1") (pintype "passive"))
    )
    (net (code "147") (name "unconnected-(P4-Pad11)") (class "Default")
      (node (ref "P4") (pin "11") (pinfunction "11_11") (pintype "passive"))
    )
    (net (code "148") (name "unconnected-(P7-Pad11)") (class "Default")
      (node (ref "P7") (pin "11") (pinfunction "11_11") (pintype "passive"))
    )
    (net (code "149") (name "unconnected-(U1-NC-Pad32)") (class "Default")
      (node (ref "U1") (pin "32") (pinfunction "NC_32") (pintype "passive+no_connect"))
    )
    (net (code "150") (name "unconnected-(U3-DATA1-Pad8)") (class "Default")
      (node (ref "U3") (pin "8") (pinfunction "DATA1_8") (pintype "passive"))
    )
    (net (code "151") (name "unconnected-(U3-DATA2-Pad1)") (class "Default")
      (node (ref "U3") (pin "1") (pinfunction "DATA2_1") (pintype "passive"))
    )
    (net (code "152") (name "unconnected-(U3-SWDECT-Pad9)") (class "Default")
      (node (ref "U3") (pin "9") (pinfunction "SWDECT_9") (pintype "passive"))
    )
    (net (code "153") (name "unconnected-(U6-SQH-Pad9)") (class "Default")
      (node (ref "U6") (pin "9") (pinfunction "SQH_9") (pintype "passive"))
    )
    (net (code "154") (name "unconnected-(U8-CTS#-Pad9)") (class "Default")
      (node (ref "U8") (pin "9") (pinfunction "CTS#_9") (pintype "passive+no_connect"))
    )
    (net (code "155") (name "unconnected-(U8-DCD#-Pad12)") (class "Default")
      (node (ref "U8") (pin "12") (pinfunction "DCD#_12") (pintype "passive+no_connect"))
    )
    (net (code "156") (name "unconnected-(U8-DSR#-Pad10)") (class "Default")
      (node (ref "U8") (pin "10") (pinfunction "DSR#_10") (pintype "passive+no_connect"))
    )
    (net (code "157") (name "unconnected-(U8-NC.-Pad7)") (class "Default")
      (node (ref "U8") (pin "7") (pinfunction "NC._7") (pintype "passive+no_connect"))
    )
    (net (code "158") (name "unconnected-(U8-NC.-Pad8)") (class "Default")
      (node (ref "U8") (pin "8") (pinfunction "NC._8") (pintype "passive+no_connect"))
    )
    (net (code "159") (name "unconnected-(U8-R232-Pad15)") (class "Default")
      (node (ref "U8") (pin "15") (pinfunction "R232_15") (pintype "passive+no_connect"))
    )
    (net (code "160") (name "unconnected-(U8-RI#-Pad11)") (class "Default")
      (node (ref "U8") (pin "11") (pinfunction "RI#_11") (pintype "passive+no_connect"))
    )
    (net (code "161") (name "unconnected-(USB C1-SBU1-PadA8)") (class "Default")
      (node (ref "USB C1") (pin "A8") (pinfunction "SBU1_A8") (pintype "passive+no_connect"))
    )
    (net (code "162") (name "unconnected-(USB C1-SBU2-PadB8)") (class "Default")
      (node (ref "USB C1") (pin "B8") (pinfunction "SBU2_B8") (pintype "passive+no_connect"))
    )
  )
)
